# SparkFun_6DoF_LSM6DSV16X.net
KiCad netlist of a schematic drawn in EAGLE
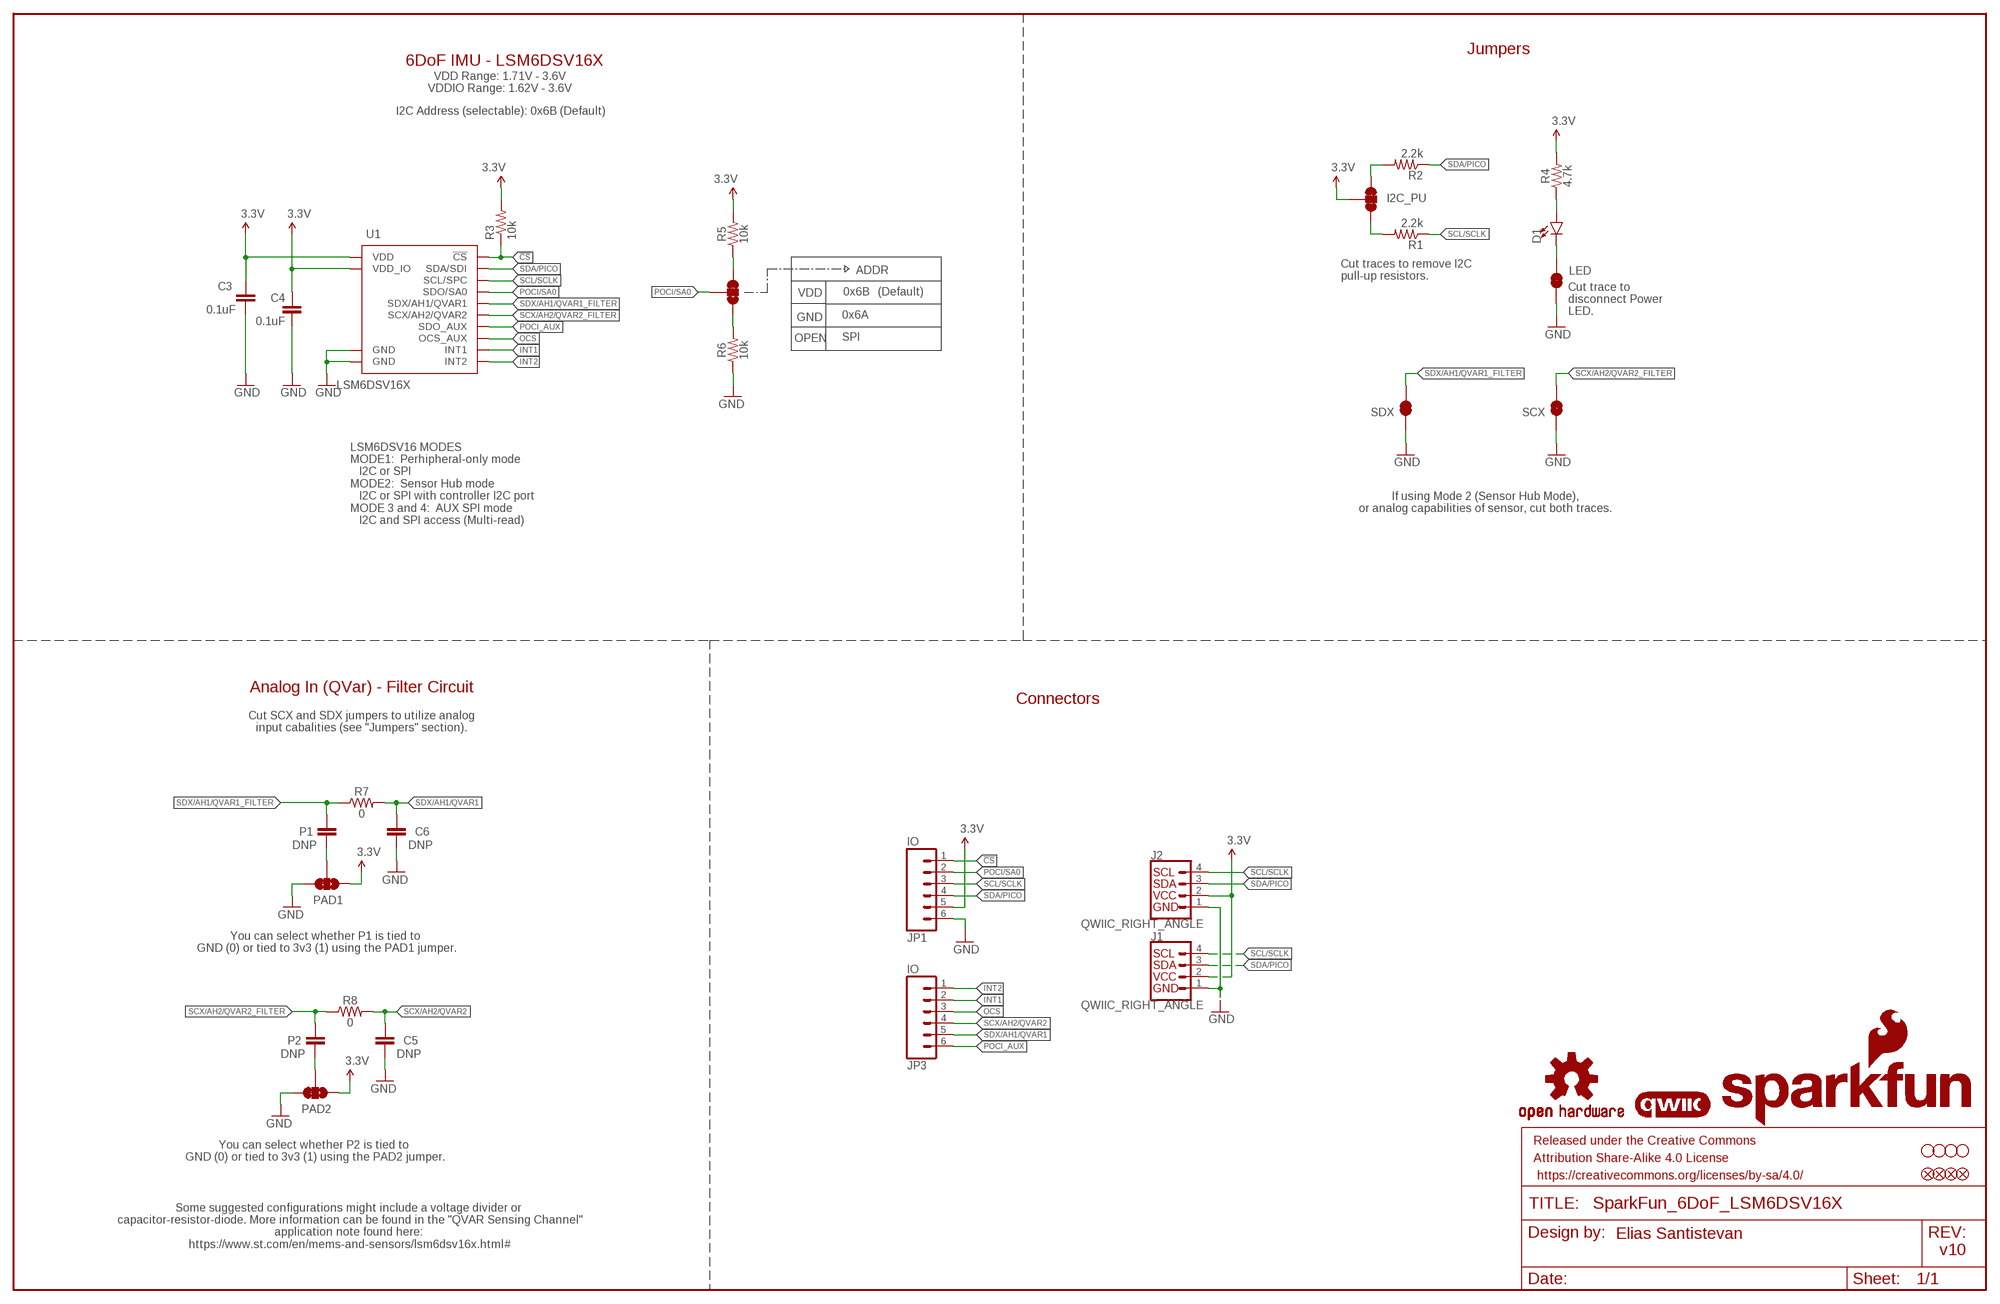
[diagram p0: schematic, sheet 1]

(export (version "E")
  (design (tool "Eeschema 10.0.6"))
  (components
    (comp (ref "ADDR")
      (value "JUMPER-SMT_3_1-NC_TRACE_SILK")
      (footprint "eagle-import:SMT-JUMPER_3_1-NC_TRACE_SILK")
      (libsource (lib "eagle-import") (part "JUMPER-SMT_3_1-NC_TRACE_SILK"))
    )
    (comp (ref "C3")
      (value "0.1uF")
      (footprint "eagle-import:0603")
      (libsource (lib "eagle-import") (part "0.1UF-0603-25V-(+80/-20%)"))
    )
    (comp (ref "C4")
      (value "0.1uF")
      (footprint "eagle-import:0603")
      (libsource (lib "eagle-import") (part "0.1UF-0603-25V-(+80/-20%)"))
    )
    (comp (ref "C5")
      (value "110pF")
      (footprint "eagle-import:0603")
      (libsource (lib "eagle-import") (part "CAP-0603"))
    )
    (comp (ref "C6")
      (value "110pF")
      (footprint "eagle-import:0603")
      (libsource (lib "eagle-import") (part "CAP-0603"))
    )
    (comp (ref "D1")
      (value "RED")
      (footprint "eagle-import:LED-0603")
      (libsource (lib "eagle-import") (part "LED-RED_0603-KB"))
    )
    (comp (ref "FD1")
      (value "FIDUCIALUFIDUCIAL")
      (footprint "eagle-import:FIDUCIAL-MICRO")
      (libsource (lib "eagle-import") (part "FIDUCIALUFIDUCIAL"))
    )
    (comp (ref "FD2")
      (value "FIDUCIALUFIDUCIAL")
      (footprint "eagle-import:FIDUCIAL-MICRO")
      (libsource (lib "eagle-import") (part "FIDUCIALUFIDUCIAL"))
    )
    (comp (ref "FID1")
      (value "FIDUCIALUFIDUCIAL")
      (footprint "eagle-import:FIDUCIAL-MICRO")
      (libsource (lib "eagle-import") (part "FIDUCIALUFIDUCIAL"))
    )
    (comp (ref "FID2")
      (value "FIDUCIALUFIDUCIAL")
      (footprint "eagle-import:FIDUCIAL-MICRO")
      (libsource (lib "eagle-import") (part "FIDUCIALUFIDUCIAL"))
    )
    (comp (ref "FRAME2")
      (value "FRAME-LEDGER")
      (footprint "eagle-import:CREATIVE_COMMONS")
      (libsource (lib "eagle-import") (part "FRAME-LEDGER"))
    )
    (comp (ref "I2C_PU")
      (value "S_MODE")
      (footprint "eagle-import:SMT-JUMPER_3_2-NC_TRACE_SILK")
      (libsource (lib "eagle-import") (part "JUMPER-SMT_3_2-NC_TRACE_SILK"))
    )
    (comp (ref "J1")
      (value "QWIIC_RIGHT_ANGLE")
      (footprint "eagle-import:JST04_1MM_RA")
      (libsource (lib "eagle-import") (part "QWIIC_CONNECTORJS-1MM"))
    )
    (comp (ref "J2")
      (value "QWIIC_RIGHT_ANGLE")
      (footprint "eagle-import:JST04_1MM_RA")
      (libsource (lib "eagle-import") (part "QWIIC_CONNECTORJS-1MM"))
    )
    (comp (ref "JP1")
      (value "IO")
      (footprint "eagle-import:1X06_NO_SILK")
      (libsource (lib "eagle-import") (part "CONN_06NO_SILK_NO_POP"))
    )
    (comp (ref "JP3")
      (value "IO")
      (footprint "eagle-import:1X06_NO_SILK")
      (libsource (lib "eagle-import") (part "CONN_06NO_SILK_NO_POP"))
    )
    (comp (ref "LED")
      (value "JUMPER-SMT_2_NC_TRACE_SILK")
      (footprint "eagle-import:SMT-JUMPER_2_NC_TRACE_SILK")
      (libsource (lib "eagle-import") (part "JUMPER-SMT_2_NC_TRACE_SILK"))
    )
    (comp (ref "LOGO1")
      (value "QWIIC_LOGO_4MM")
      (footprint "eagle-import:QWIIC_4MM")
      (libsource (lib "eagle-import") (part "QWIIC_LOGO_4MM"))
    )
    (comp (ref "LOGO2")
      (value "OSHW-LOGOMINI")
      (footprint "eagle-import:OSHW-LOGO-MINI")
      (libsource (lib "eagle-import") (part "OSHW-LOGOMINI"))
    )
    (comp (ref "LOGO3")
      (value "SFE_LOGO_NAME_FLAMEBLANK")
      (footprint "eagle-import:BLANK")
      (libsource (lib "eagle-import") (part "SFE_LOGO_NAME_FLAMEBLANK"))
    )
    (comp (ref "P1")
      (value "110pF")
      (footprint "eagle-import:0603")
      (libsource (lib "eagle-import") (part "CAP-0603"))
    )
    (comp (ref "P2")
      (value "110pF")
      (footprint "eagle-import:0603")
      (libsource (lib "eagle-import") (part "CAP-0603"))
    )
    (comp (ref "PAD1")
      (value "JUMPER-SMT_3_1-NC_TRACE_SILK")
      (footprint "eagle-import:SMT-JUMPER_3_1-NC_TRACE_SILK")
      (libsource (lib "eagle-import") (part "JUMPER-SMT_3_1-NC_TRACE_SILK"))
    )
    (comp (ref "PAD2")
      (value "JUMPER-SMT_3_1-NC_TRACE_SILK")
      (footprint "eagle-import:SMT-JUMPER_3_1-NC_TRACE_SILK")
      (libsource (lib "eagle-import") (part "JUMPER-SMT_3_1-NC_TRACE_SILK"))
    )
    (comp (ref "R1")
      (value "2.2k")
      (footprint "eagle-import:0603")
      (libsource (lib "eagle-import") (part "2.2KOHM-0603-1/10W-1%"))
    )
    (comp (ref "R2")
      (value "2.2k")
      (footprint "eagle-import:0603")
      (libsource (lib "eagle-import") (part "2.2KOHM-0603-1/10W-1%"))
    )
    (comp (ref "R3")
      (value "10k")
      (footprint "eagle-import:0603")
      (libsource (lib "eagle-import") (part "10KOHM-0603-1/10W-1%"))
    )
    (comp (ref "R4")
      (value "4.7k")
      (footprint "eagle-import:0603")
      (libsource (lib "eagle-import") (part "4.7KOHM-0603-1/10W-1%"))
    )
    (comp (ref "R5")
      (value "10k")
      (footprint "eagle-import:0603")
      (libsource (lib "eagle-import") (part "10KOHM-0603-1/10W-1%"))
    )
    (comp (ref "R6")
      (value "10k")
      (footprint "eagle-import:0603")
      (libsource (lib "eagle-import") (part "10KOHM-0603-1/10W-1%"))
    )
    (comp (ref "R7")
      (value "0")
      (footprint "eagle-import:0603")
      (libsource (lib "eagle-import") (part "0OHM-0603-1/10W"))
    )
    (comp (ref "R8")
      (value "0")
      (footprint "eagle-import:0603")
      (libsource (lib "eagle-import") (part "0OHM-0603-1/10W"))
    )
    (comp (ref "SCX")
      (value "JUMPER-SMT_2_NC_TRACE_SILK")
      (footprint "eagle-import:SMT-JUMPER_2_NC_TRACE_SILK")
      (libsource (lib "eagle-import") (part "JUMPER-SMT_2_NC_TRACE_SILK"))
    )
    (comp (ref "SDX")
      (value "JUMPER-SMT_2_NC_TRACE_SILK")
      (footprint "eagle-import:SMT-JUMPER_2_NC_TRACE_SILK")
      (libsource (lib "eagle-import") (part "JUMPER-SMT_2_NC_TRACE_SILK"))
    )
    (comp (ref "STANDOFF1")
      (value "STAND-OFFTIGHT")
      (footprint "eagle-import:STAND-OFF-TIGHT")
      (libsource (lib "eagle-import") (part "STAND-OFFTIGHT"))
    )
    (comp (ref "STANDOFF2")
      (value "STAND-OFFTIGHT")
      (footprint "eagle-import:STAND-OFF-TIGHT")
      (libsource (lib "eagle-import") (part "STAND-OFFTIGHT"))
    )
    (comp (ref "STANDOFF3")
      (value "STAND-OFFTIGHT")
      (footprint "eagle-import:STAND-OFF-TIGHT")
      (libsource (lib "eagle-import") (part "STAND-OFFTIGHT"))
    )
    (comp (ref "STANDOFF4")
      (value "STAND-OFFTIGHT")
      (footprint "eagle-import:STAND-OFF-TIGHT")
      (libsource (lib "eagle-import") (part "STAND-OFFTIGHT"))
    )
    (comp (ref "U1")
      (value "LSM6DSV16X")
      (footprint "eagle-import:LGA-14L")
      (libsource (lib "eagle-import") (part "LSM6DSV16X"))
    )
  )
  (nets
    (net (code "1") (name "/~{CS}") (class "Default")
      (node (ref "JP1") (pin "1") (pinfunction "1_1") (pintype "passive"))
      (node (ref "R3") (pin "1") (pinfunction "1_1") (pintype "passive"))
      (node (ref "U1") (pin "P12") (pinfunction "~{CS}_P12") (pintype "bidirectional"))
    )
    (net (code "2") (name "3.3V") (class "Default")
      (node (ref "C3") (pin "1") (pinfunction "1_1") (pintype "passive"))
      (node (ref "C4") (pin "1") (pinfunction "1_1") (pintype "passive"))
      (node (ref "I2C_PU") (pin "2") (pinfunction "2_2") (pintype "passive"))
      (node (ref "J1") (pin "2") (pinfunction "2_2") (pintype "power_in"))
      (node (ref "J2") (pin "2") (pinfunction "2_2") (pintype "power_in"))
      (node (ref "JP1") (pin "5") (pinfunction "5_5") (pintype "passive"))
      (node (ref "PAD1") (pin "1") (pinfunction "1_1") (pintype "passive"))
      (node (ref "PAD2") (pin "1") (pinfunction "1_1") (pintype "passive"))
      (node (ref "R3") (pin "2") (pinfunction "2_2") (pintype "passive"))
      (node (ref "R4") (pin "2") (pinfunction "2_2") (pintype "passive"))
      (node (ref "R5") (pin "2") (pinfunction "2_2") (pintype "passive"))
      (node (ref "U1") (pin "P5") (pinfunction "VDD_IO_P5") (pintype "power_in"))
      (node (ref "U1") (pin "P8") (pinfunction "VDD_P8") (pintype "power_in"))
    )
    (net (code "3") (name "GND") (class "Default")
      (node (ref "C3") (pin "2") (pinfunction "2_2") (pintype "passive"))
      (node (ref "C4") (pin "2") (pinfunction "2_2") (pintype "passive"))
      (node (ref "C5") (pin "2") (pinfunction "2_2") (pintype "passive"))
      (node (ref "C6") (pin "2") (pinfunction "2_2") (pintype "passive"))
      (node (ref "J1") (pin "1") (pinfunction "1_1") (pintype "power_in"))
      (node (ref "J2") (pin "1") (pinfunction "1_1") (pintype "power_in"))
      (node (ref "JP1") (pin "6") (pinfunction "6_6") (pintype "passive"))
      (node (ref "LED") (pin "1") (pinfunction "1_1") (pintype "passive"))
      (node (ref "PAD1") (pin "3") (pinfunction "3_3") (pintype "passive"))
      (node (ref "PAD2") (pin "3") (pinfunction "3_3") (pintype "passive"))
      (node (ref "R6") (pin "1") (pinfunction "1_1") (pintype "passive"))
      (node (ref "SCX") (pin "1") (pinfunction "1_1") (pintype "passive"))
      (node (ref "SDX") (pin "1") (pinfunction "1_1") (pintype "passive"))
      (node (ref "U1") (pin "P6") (pinfunction "GND_P6") (pintype "power_in"))
      (node (ref "U1") (pin "P7") (pinfunction "GND_P7") (pintype "power_in"))
    )
    (net (code "4") (name "INT1") (class "Default")
      (node (ref "JP3") (pin "2") (pinfunction "2_2") (pintype "passive"))
      (node (ref "U1") (pin "P4") (pinfunction "INT1_P4") (pintype "bidirectional"))
    )
    (net (code "5") (name "INT2") (class "Default")
      (node (ref "JP3") (pin "1") (pinfunction "1_1") (pintype "passive"))
      (node (ref "U1") (pin "P9") (pinfunction "INT2_P9") (pintype "bidirectional"))
    )
    (net (code "6") (name "Net-(ADDR-Pad1)") (class "Default")
      (node (ref "ADDR") (pin "1") (pinfunction "1_1") (pintype "passive"))
      (node (ref "R6") (pin "2") (pinfunction "2_2") (pintype "passive"))
    )
    (net (code "7") (name "Net-(ADDR-Pad3)") (class "Default")
      (node (ref "ADDR") (pin "3") (pinfunction "3_3") (pintype "passive"))
      (node (ref "R5") (pin "1") (pinfunction "1_1") (pintype "passive"))
    )
    (net (code "8") (name "Net-(D1-PadA)") (class "Default")
      (node (ref "D1") (pin "A") (pinfunction "A_A") (pintype "passive"))
      (node (ref "R4") (pin "1") (pinfunction "1_1") (pintype "passive"))
    )
    (net (code "9") (name "Net-(D1-PadC)") (class "Default")
      (node (ref "D1") (pin "C") (pinfunction "C_C") (pintype "passive"))
      (node (ref "LED") (pin "2") (pinfunction "2_2") (pintype "passive"))
    )
    (net (code "10") (name "Net-(I2C_PU-Pad1)") (class "Default")
      (node (ref "I2C_PU") (pin "1") (pinfunction "1_1") (pintype "passive"))
      (node (ref "R1") (pin "2") (pinfunction "2_2") (pintype "passive"))
    )
    (net (code "11") (name "Net-(I2C_PU-Pad3)") (class "Default")
      (node (ref "I2C_PU") (pin "3") (pinfunction "3_3") (pintype "passive"))
      (node (ref "R2") (pin "2") (pinfunction "2_2") (pintype "passive"))
    )
    (net (code "12") (name "Net-(P1-Pad2)") (class "Default")
      (node (ref "P1") (pin "2") (pinfunction "2_2") (pintype "passive"))
      (node (ref "PAD1") (pin "2") (pinfunction "2_2") (pintype "passive"))
    )
    (net (code "13") (name "Net-(P2-Pad2)") (class "Default")
      (node (ref "P2") (pin "2") (pinfunction "2_2") (pintype "passive"))
      (node (ref "PAD2") (pin "2") (pinfunction "2_2") (pintype "passive"))
    )
    (net (code "14") (name "OCS") (class "Default")
      (node (ref "JP3") (pin "3") (pinfunction "3_3") (pintype "passive"))
      (node (ref "U1") (pin "P10") (pinfunction "OCS_AUX_P10") (pintype "bidirectional"))
    )
    (net (code "15") (name "POCI_AUX") (class "Default")
      (node (ref "JP3") (pin "6") (pinfunction "6_6") (pintype "passive"))
      (node (ref "U1") (pin "P11") (pinfunction "SDO_AUX_P11") (pintype "bidirectional"))
    )
    (net (code "16") (name "POCI{slash}SA0") (class "Default")
      (node (ref "ADDR") (pin "2") (pinfunction "2_2") (pintype "passive"))
      (node (ref "JP1") (pin "2") (pinfunction "2_2") (pintype "passive"))
      (node (ref "U1") (pin "P1") (pinfunction "SDO/SA0_P1") (pintype "bidirectional"))
    )
    (net (code "17") (name "SCL{slash}SCLK") (class "Default")
      (node (ref "J1") (pin "4") (pinfunction "4_4") (pintype "passive"))
      (node (ref "J2") (pin "4") (pinfunction "4_4") (pintype "passive"))
      (node (ref "JP1") (pin "3") (pinfunction "3_3") (pintype "passive"))
      (node (ref "R1") (pin "1") (pinfunction "1_1") (pintype "passive"))
      (node (ref "U1") (pin "P13") (pinfunction "SCL/SPC_P13") (pintype "bidirectional"))
    )
    (net (code "18") (name "SCX{slash}AH2{slash}QVAR2") (class "Default")
      (node (ref "C5") (pin "1") (pinfunction "1_1") (pintype "passive"))
      (node (ref "JP3") (pin "4") (pinfunction "4_4") (pintype "passive"))
      (node (ref "R8") (pin "2") (pinfunction "2_2") (pintype "passive"))
    )
    (net (code "19") (name "SCX{slash}AH2{slash}QVAR2_FILTER") (class "Default")
      (node (ref "P2") (pin "1") (pinfunction "1_1") (pintype "passive"))
      (node (ref "R8") (pin "1") (pinfunction "1_1") (pintype "passive"))
      (node (ref "SCX") (pin "2") (pinfunction "2_2") (pintype "passive"))
      (node (ref "U1") (pin "P3") (pinfunction "SCX/AH2/QVAR2_P3") (pintype "bidirectional"))
    )
    (net (code "20") (name "SDA{slash}PICO") (class "Default")
      (node (ref "J1") (pin "3") (pinfunction "3_3") (pintype "passive"))
      (node (ref "J2") (pin "3") (pinfunction "3_3") (pintype "passive"))
      (node (ref "JP1") (pin "4") (pinfunction "4_4") (pintype "passive"))
      (node (ref "R2") (pin "1") (pinfunction "1_1") (pintype "passive"))
      (node (ref "U1") (pin "P14") (pinfunction "SDA/SDI_P14") (pintype "bidirectional"))
    )
    (net (code "21") (name "SDX{slash}AH1{slash}QVAR1") (class "Default")
      (node (ref "C6") (pin "1") (pinfunction "1_1") (pintype "passive"))
      (node (ref "JP3") (pin "5") (pinfunction "5_5") (pintype "passive"))
      (node (ref "R7") (pin "2") (pinfunction "2_2") (pintype "passive"))
    )
    (net (code "22") (name "SDX{slash}AH1{slash}QVAR1_FILTER") (class "Default")
      (node (ref "P1") (pin "1") (pinfunction "1_1") (pintype "passive"))
      (node (ref "R7") (pin "1") (pinfunction "1_1") (pintype "passive"))
      (node (ref "SDX") (pin "2") (pinfunction "2_2") (pintype "passive"))
      (node (ref "U1") (pin "P2") (pinfunction "SDX/AH1/QVAR1_P2") (pintype "bidirectional"))
    )
  )
)
